# ExpressCarduino-Basic.net
KiCad netlist of a schematic drawn in EAGLE
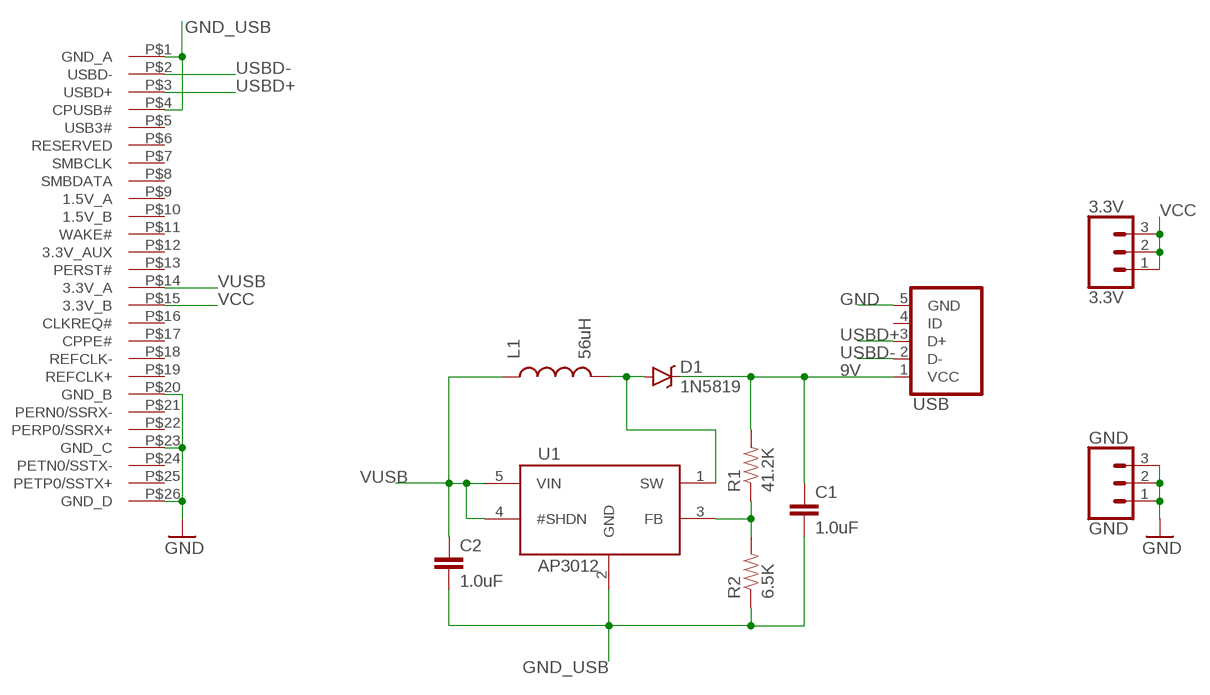
[diagram p0: schematic, sheet 1]

(export (version "E")
  (design (tool "Eeschema 10.0.6"))
  (components
    (comp (ref "3.3V")
      (value "3.3V")
      (footprint "eagle-import:1X03")
      (libsource (lib "eagle-import") (part "CONN_03"))
    )
    (comp (ref "C1")
      (value "1.0uF")
      (footprint "eagle-import:0603-CAP")
      (libsource (lib "eagle-import") (part "1.0UF-16V-10%(0603)"))
    )
    (comp (ref "C2")
      (value "1.0uF")
      (footprint "eagle-import:0603-CAP")
      (libsource (lib "eagle-import") (part "1.0UF-16V-10%(0603)"))
    )
    (comp (ref "D1")
      (value "1N5819")
      (footprint "eagle-import:SOD-123")
      (libsource (lib "eagle-import") (part "DIODE-SCHOTTKY"))
    )
    (comp (ref "GND")
      (value "GND")
      (footprint "eagle-import:1X03")
      (libsource (lib "eagle-import") (part "CONN_03"))
    )
    (comp (ref "L1")
      (value "56uH")
      (footprint "eagle-import:SDR0403")
      (libsource (lib "eagle-import") (part "INDUCTORSDR0403-560KL"))
    )
    (comp (ref "R1")
      (value "41.2K")
      (footprint "eagle-import:0805")
      (libsource (lib "eagle-import") (part "0.22OHM-1/4W-1%(0805)"))
    )
    (comp (ref "R2")
      (value "6.5K")
      (footprint "eagle-import:0805")
      (libsource (lib "eagle-import") (part "0.22OHM-1/4W-1%(0805)"))
    )
    (comp (ref "U$1")
      (value "EXPRESSCARD34")
      (footprint "eagle-import:EXPRESSCARD34")
      (libsource (lib "eagle-import") (part "EXPRESSCARD34"))
    )
    (comp (ref "U1")
      (value "AP3012")
      (footprint "eagle-import:SOT23-5")
      (libsource (lib "eagle-import") (part "AP3012"))
    )
    (comp (ref "USB")
      (value "USB_MICROB_PLUG\"")
      (footprint "eagle-import:MICRO-B-RA-SMT")
      (libsource (lib "eagle-import") (part "USB_MICROB_PLUG{dblquote}"))
    )
  )
  (nets
    (net (code "1") (name "/1.5V_A") (class "Default")
      (node (ref "U$1") (pin "P$9") (pinfunction "1.5V_A_P$9") (pintype "power_in"))
    )
    (net (code "2") (name "/1.5V_B") (class "Default")
      (node (ref "U$1") (pin "P$10") (pinfunction "1.5V_B_P$10") (pintype "power_in"))
    )
    (net (code "3") (name "/3.3V_AUX") (class "Default")
      (node (ref "U$1") (pin "P$12") (pinfunction "3.3V_AUX_P$12") (pintype "power_in"))
    )
    (net (code "4") (name "/9V") (class "Default")
      (node (ref "C1") (pin "1") (pinfunction "1_1") (pintype "passive"))
      (node (ref "D1") (pin "C") (pinfunction "C_C") (pintype "passive"))
      (node (ref "R1") (pin "2") (pinfunction "2_2") (pintype "passive"))
      (node (ref "USB") (pin "1") (pinfunction "VCC_1") (pintype "bidirectional"))
    )
    (net (code "5") (name "/GND_USB") (class "Default")
      (node (ref "C1") (pin "2") (pinfunction "2_2") (pintype "passive"))
      (node (ref "C2") (pin "2") (pinfunction "2_2") (pintype "passive"))
      (node (ref "R2") (pin "1") (pinfunction "1_1") (pintype "passive"))
      (node (ref "U$1") (pin "P$1") (pinfunction "GND_A_P$1") (pintype "power_in"))
      (node (ref "U$1") (pin "P$4") (pinfunction "CPUSB#_P$4") (pintype "input"))
      (node (ref "U1") (pin "2") (pinfunction "GND_2") (pintype "power_in"))
    )
    (net (code "6") (name "/USBD+") (class "Default")
      (node (ref "U$1") (pin "P$3") (pinfunction "USBD+_P$3") (pintype "bidirectional"))
      (node (ref "USB") (pin "3") (pinfunction "D+_3") (pintype "bidirectional"))
    )
    (net (code "7") (name "/USBD-") (class "Default")
      (node (ref "U$1") (pin "P$2") (pinfunction "USBD-_P$2") (pintype "bidirectional"))
      (node (ref "USB") (pin "2") (pinfunction "D-_2") (pintype "bidirectional"))
    )
    (net (code "8") (name "/VCC") (class "Default")
      (node (ref "3.3V") (pin "1") (pinfunction "1_1") (pintype "passive"))
      (node (ref "3.3V") (pin "2") (pinfunction "2_2") (pintype "passive"))
      (node (ref "3.3V") (pin "3") (pinfunction "3_3") (pintype "passive"))
      (node (ref "U$1") (pin "P$15") (pinfunction "3.3V_B_P$15") (pintype "power_in"))
    )
    (net (code "9") (name "/VUSB") (class "Default")
      (node (ref "C2") (pin "1") (pinfunction "1_1") (pintype "passive"))
      (node (ref "L1") (pin "P$1") (pinfunction "1_P$1") (pintype "passive"))
      (node (ref "U$1") (pin "P$14") (pinfunction "3.3V_A_P$14") (pintype "power_in"))
      (node (ref "U1") (pin "4") (pinfunction "#SHDN_4") (pintype "input"))
      (node (ref "U1") (pin "5") (pinfunction "VIN_5") (pintype "power_in"))
    )
    (net (code "10") (name "GND") (class "Default")
      (node (ref "GND") (pin "1") (pinfunction "1_1") (pintype "passive"))
      (node (ref "GND") (pin "2") (pinfunction "2_2") (pintype "passive"))
      (node (ref "GND") (pin "3") (pinfunction "3_3") (pintype "passive"))
      (node (ref "U$1") (pin "P$20") (pinfunction "GND_B_P$20") (pintype "power_in"))
      (node (ref "U$1") (pin "P$23") (pinfunction "GND_C_P$23") (pintype "power_in"))
      (node (ref "U$1") (pin "P$26") (pinfunction "GND_D_P$26") (pintype "power_in"))
      (node (ref "USB") (pin "5") (pinfunction "GND_5") (pintype "bidirectional"))
    )
    (net (code "11") (name "Net-(L1-2)") (class "Default")
      (node (ref "D1") (pin "A") (pinfunction "A_A") (pintype "passive"))
      (node (ref "L1") (pin "P$2") (pinfunction "2_P$2") (pintype "passive"))
      (node (ref "U1") (pin "1") (pinfunction "SW_1") (pintype "output"))
    )
    (net (code "12") (name "Net-(U1-FB)") (class "Default")
      (node (ref "R1") (pin "1") (pinfunction "1_1") (pintype "passive"))
      (node (ref "R2") (pin "2") (pinfunction "2_2") (pintype "passive"))
      (node (ref "U1") (pin "3") (pinfunction "FB_3") (pintype "input"))
    )
    (net (code "13") (name "unconnected-(U$1-CLKREQ#-PadP$16)") (class "Default")
      (node (ref "U$1") (pin "P$16") (pinfunction "CLKREQ#_P$16") (pintype "input"))
    )
    (net (code "14") (name "unconnected-(U$1-CPPE#-PadP$17)") (class "Default")
      (node (ref "U$1") (pin "P$17") (pinfunction "CPPE#_P$17") (pintype "input"))
    )
    (net (code "15") (name "unconnected-(U$1-PERN0{slash}SSRX--PadP$21)") (class "Default")
      (node (ref "U$1") (pin "P$21") (pinfunction "PERN0/SSRX-_P$21") (pintype "input"))
    )
    (net (code "16") (name "unconnected-(U$1-PERP0{slash}SSRX+-PadP$22)") (class "Default")
      (node (ref "U$1") (pin "P$22") (pinfunction "PERP0/SSRX+_P$22") (pintype "input"))
    )
    (net (code "17") (name "unconnected-(U$1-PERST#-PadP$13)") (class "Default")
      (node (ref "U$1") (pin "P$13") (pinfunction "PERST#_P$13") (pintype "output"))
    )
    (net (code "18") (name "unconnected-(U$1-PETN0{slash}SSTX--PadP$24)") (class "Default")
      (node (ref "U$1") (pin "P$24") (pinfunction "PETN0/SSTX-_P$24") (pintype "output"))
    )
    (net (code "19") (name "unconnected-(U$1-PETP0{slash}SSTX+-PadP$25)") (class "Default")
      (node (ref "U$1") (pin "P$25") (pinfunction "PETP0/SSTX+_P$25") (pintype "output"))
    )
    (net (code "20") (name "unconnected-(U$1-REFCLK+-PadP$19)") (class "Default")
      (node (ref "U$1") (pin "P$19") (pinfunction "REFCLK+_P$19") (pintype "output"))
    )
    (net (code "21") (name "unconnected-(U$1-REFCLK--PadP$18)") (class "Default")
      (node (ref "U$1") (pin "P$18") (pinfunction "REFCLK-_P$18") (pintype "output"))
    )
    (net (code "22") (name "unconnected-(U$1-RESERVED-PadP$6)") (class "Default")
      (node (ref "U$1") (pin "P$6") (pinfunction "RESERVED_P$6") (pintype "no_connect"))
    )
    (net (code "23") (name "unconnected-(U$1-SMBCLK-PadP$7)") (class "Default")
      (node (ref "U$1") (pin "P$7") (pinfunction "SMBCLK_P$7") (pintype "bidirectional"))
    )
    (net (code "24") (name "unconnected-(U$1-SMBDATA-PadP$8)") (class "Default")
      (node (ref "U$1") (pin "P$8") (pinfunction "SMBDATA_P$8") (pintype "bidirectional"))
    )
    (net (code "25") (name "unconnected-(U$1-USB3#-PadP$5)") (class "Default")
      (node (ref "U$1") (pin "P$5") (pinfunction "USB3#_P$5") (pintype "input"))
    )
    (net (code "26") (name "unconnected-(U$1-WAKE#-PadP$11)") (class "Default")
      (node (ref "U$1") (pin "P$11") (pinfunction "WAKE#_P$11") (pintype "input"))
    )
    (net (code "27") (name "unconnected-(USB-ID-Pad4)") (class "Default")
      (node (ref "USB") (pin "4") (pinfunction "ID_4") (pintype "bidirectional"))
    )
  )
)
